# LED.net
KiCad netlist of a schematic drawn in Altium Designer
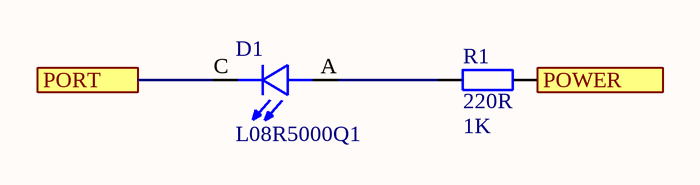
[diagram p0: LED.SchDoc]

(export (version "E")
  (design (tool "Eeschema 10.0.6"))
  (components
    (comp (ref "D1")
      (value "L08R5000Q1")
      (footprint "LEDRD254W57D500H1070")
      (fields (field (name "MF") "LED Technology"))
      (libsource (lib "LED") (part "L08R5000Q1"))
    )
    (comp (ref "R1")
      (value "220R")
      (footprint "AXIAL-0.4")
      (description "Resistor")
      (fields (field (name "ALTIUM_VALUE") "1K") (field (name "PUBLISHER") "Altium Limited"))
      (libsource (lib "Miscellaneous Devices") (part "Res2"))
    )
  )
  (nets
    (net (code "1") (name "/PORT") (class "Default")
      (node (ref "D1") (pin "C") (pinfunction "C_C") (pintype "passive"))
    )
    (net (code "2") (name "/POWER") (class "Default")
      (node (ref "R1") (pin "2") (pinfunction "2_2") (pintype "passive"))
    )
    (net (code "3") (name "Net-(D1-PadA)") (class "Default")
      (node (ref "D1") (pin "A") (pinfunction "A_A") (pintype "passive"))
      (node (ref "R1") (pin "1") (pinfunction "1_1") (pintype "passive"))
    )
  )
)
